# sdr_3157.net
KiCad netlist of a schematic drawn in EAGLE
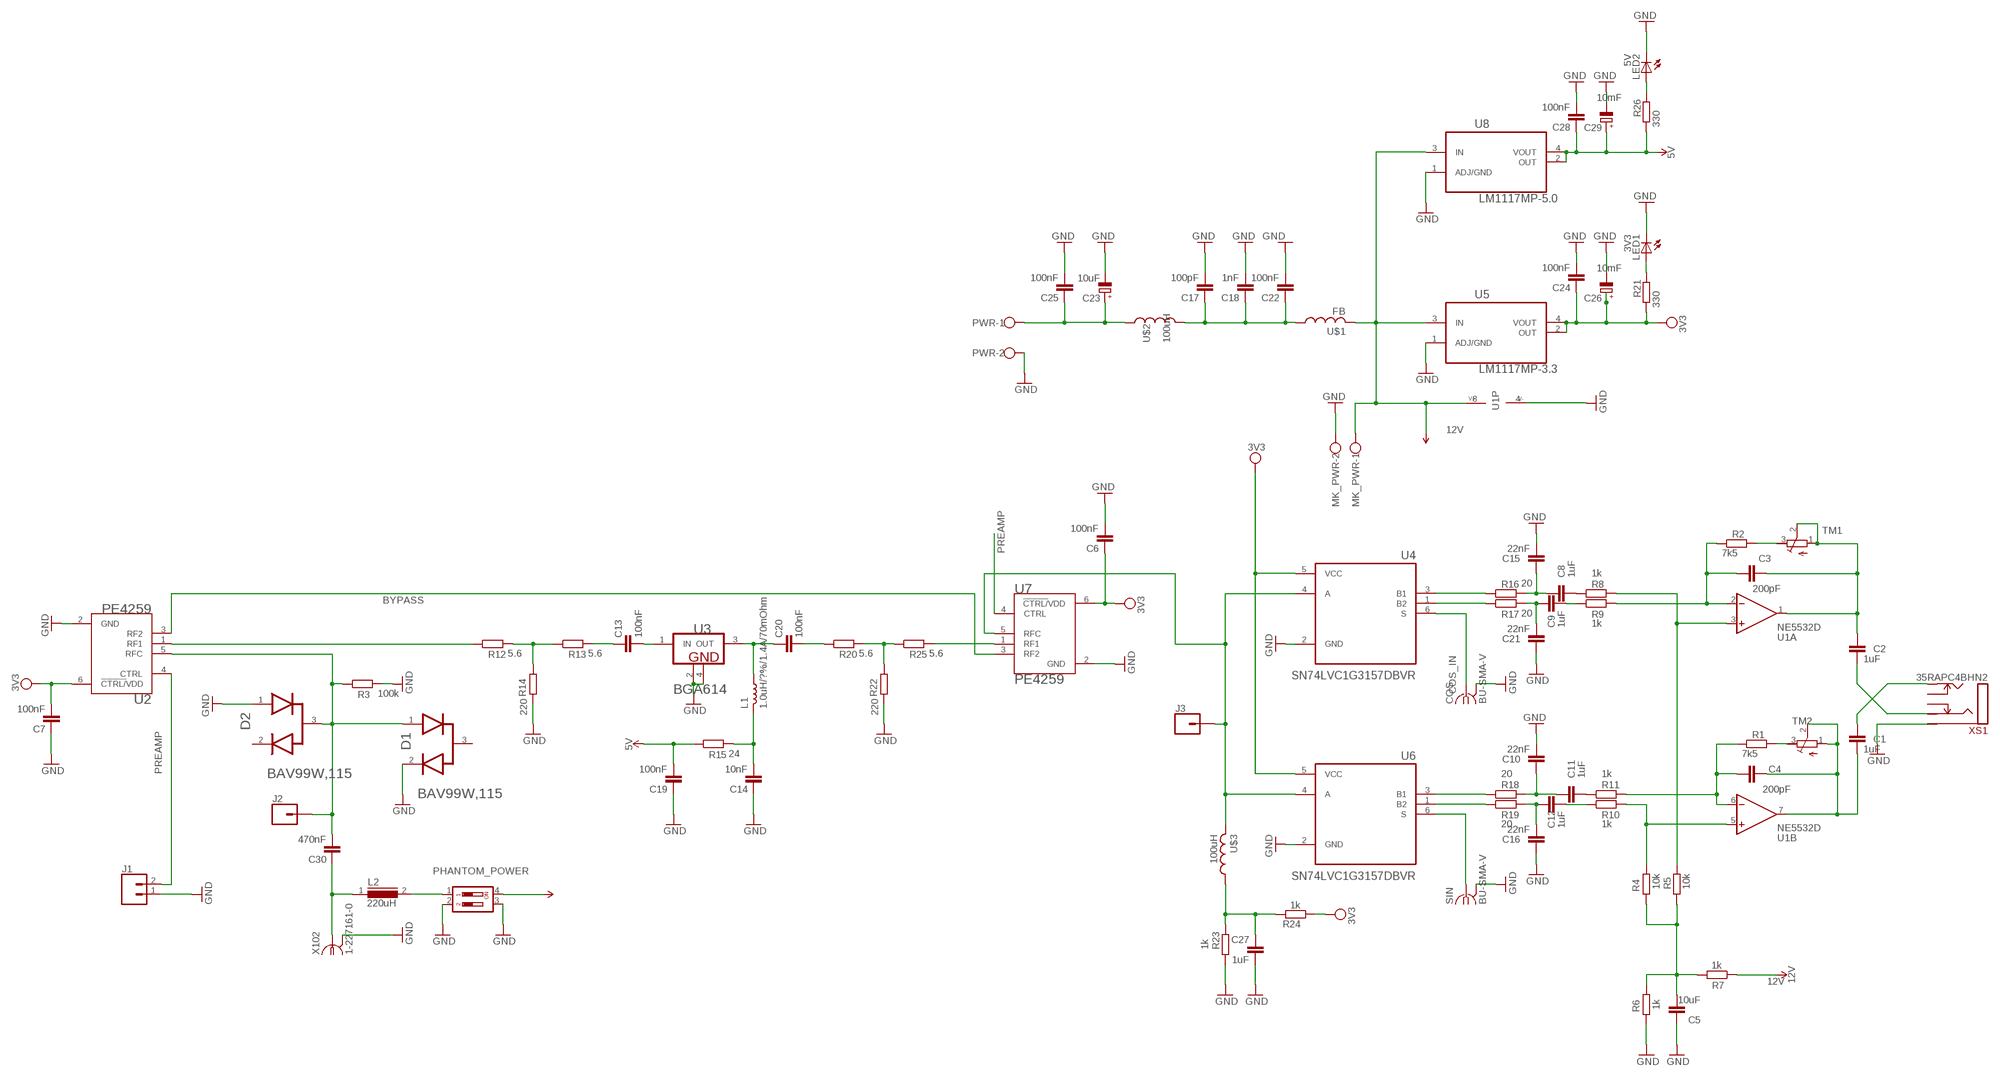
[diagram p0: schematic, sheet 1]

(export (version "E")
  (design (tool "Eeschema 10.0.6"))
  (components
    (comp (ref "C1")
      (value "1uF")
      (footprint "eagle-import:C050-045X075")
      (libsource (lib "eagle-import") (part "C-EU050-045X075"))
    )
    (comp (ref "C2")
      (value "1uF")
      (footprint "eagle-import:C050-045X075")
      (libsource (lib "eagle-import") (part "C-EU050-045X075"))
    )
    (comp (ref "C3")
      (value "200pF")
      (footprint "eagle-import:C050-045X075")
      (libsource (lib "eagle-import") (part "C-EU050-045X075"))
    )
    (comp (ref "C4")
      (value "200pF")
      (footprint "eagle-import:C050-045X075")
      (libsource (lib "eagle-import") (part "C-EU050-045X075"))
    )
    (comp (ref "C5")
      (value "10uF")
      (footprint "eagle-import:C0805")
      (libsource (lib "eagle-import") (part "C-EUC0805"))
    )
    (comp (ref "C6")
      (value "100nF")
      (footprint "eagle-import:C0805")
      (libsource (lib "eagle-import") (part "C-EUC0805"))
    )
    (comp (ref "C7")
      (value "100nF")
      (footprint "eagle-import:C0805")
      (libsource (lib "eagle-import") (part "C-EUC0805"))
    )
    (comp (ref "C8")
      (value "1uF")
      (footprint "eagle-import:C0805")
      (libsource (lib "eagle-import") (part "C-EUC0805"))
    )
    (comp (ref "C9")
      (value "1uF")
      (footprint "eagle-import:C0805")
      (libsource (lib "eagle-import") (part "C-EUC0805"))
    )
    (comp (ref "C10")
      (value "22nF")
      (footprint "eagle-import:C0805")
      (libsource (lib "eagle-import") (part "C-EUC0805"))
    )
    (comp (ref "C11")
      (value "1uF")
      (footprint "eagle-import:C0805")
      (libsource (lib "eagle-import") (part "C-EUC0805"))
    )
    (comp (ref "C12")
      (value "1uF")
      (footprint "eagle-import:C0805")
      (libsource (lib "eagle-import") (part "C-EUC0805"))
    )
    (comp (ref "C13")
      (value "100nF")
      (footprint "eagle-import:C0805")
      (libsource (lib "eagle-import") (part "C-EUC0805"))
    )
    (comp (ref "C14")
      (value "10nF")
      (footprint "eagle-import:C0805")
      (libsource (lib "eagle-import") (part "C-EUC0805"))
    )
    (comp (ref "C15")
      (value "22nF")
      (footprint "eagle-import:C0805")
      (libsource (lib "eagle-import") (part "C-EUC0805"))
    )
    (comp (ref "C16")
      (value "22nF")
      (footprint "eagle-import:C0805")
      (libsource (lib "eagle-import") (part "C-EUC0805"))
    )
    (comp (ref "C17")
      (value "100pF")
      (footprint "eagle-import:C0805")
      (libsource (lib "eagle-import") (part "C-EUC0805"))
    )
    (comp (ref "C18")
      (value "1nF")
      (footprint "eagle-import:C0805")
      (libsource (lib "eagle-import") (part "C-EUC0805"))
    )
    (comp (ref "C19")
      (value "100nF")
      (footprint "eagle-import:C0805")
      (libsource (lib "eagle-import") (part "C-EUC0805"))
    )
    (comp (ref "C20")
      (value "100nF")
      (footprint "eagle-import:C0805")
      (libsource (lib "eagle-import") (part "C-EUC0805"))
    )
    (comp (ref "C21")
      (value "22nF")
      (footprint "eagle-import:C0805")
      (libsource (lib "eagle-import") (part "C-EUC0805"))
    )
    (comp (ref "C22")
      (value "100nF")
      (footprint "eagle-import:C0805")
      (libsource (lib "eagle-import") (part "C-EUC0805"))
    )
    (comp (ref "C23")
      (value "10uF")
      (footprint "eagle-import:SMC_C")
      (libsource (lib "eagle-import") (part "CPOL-EUSMCC"))
    )
    (comp (ref "C24")
      (value "100nF")
      (footprint "eagle-import:C0805")
      (libsource (lib "eagle-import") (part "C-EUC0805"))
    )
    (comp (ref "C25")
      (value "100nF")
      (footprint "eagle-import:C0805")
      (libsource (lib "eagle-import") (part "C-EUC0805"))
    )
    (comp (ref "C26")
      (value "10mF")
      (footprint "eagle-import:SMC_C")
      (libsource (lib "eagle-import") (part "CPOL-EUSMCC"))
    )
    (comp (ref "C27")
      (value "1uF")
      (footprint "eagle-import:C0805")
      (libsource (lib "eagle-import") (part "C-EUC0805"))
    )
    (comp (ref "C28")
      (value "100nF")
      (footprint "eagle-import:C0805")
      (libsource (lib "eagle-import") (part "C-EUC0805"))
    )
    (comp (ref "C29")
      (value "10mF")
      (footprint "eagle-import:SMC_C")
      (libsource (lib "eagle-import") (part "CPOL-EUSMCC"))
    )
    (comp (ref "C30")
      (value "470nF")
      (footprint "eagle-import:C0805")
      (libsource (lib "eagle-import") (part "C-EUC0805"))
    )
    (comp (ref "COS")
      (value "BU-SMA-V")
      (footprint "eagle-import:BU-SMA-V")
      (libsource (lib "eagle-import") (part "BU-SMA-V"))
    )
    (comp (ref "D1")
      (value "NEXPERIA_BAV99W,115NEXPERIA_BAV99W,115_0_0")
      (footprint "eagle-import:NEXPERIA_BAV99W,115_0")
      (fields
        (field (name "3DS_PART_NUMBER") "412-00001")
        (field (name "DIGIKEY_PART_NUMBER") "1727-2915-1-ND")
        (field (name "MF") "Nexperia")
      )
      (libsource (lib "eagle-import") (part "NEXPERIA_BAV99W,115NEXPERIA_BAV99W,115_0_0"))
    )
    (comp (ref "D2")
      (value "NEXPERIA_BAV99W,115NEXPERIA_BAV99W,115_0_0")
      (footprint "eagle-import:NEXPERIA_BAV99W,115_0")
      (fields
        (field (name "3DS_PART_NUMBER") "412-00001")
        (field (name "DIGIKEY_PART_NUMBER") "1727-2915-1-ND")
        (field (name "MF") "Nexperia")
      )
      (libsource (lib "eagle-import") (part "NEXPERIA_BAV99W,115NEXPERIA_BAV99W,115_0_0"))
    )
    (comp (ref "J1")
      (value "CONN_02")
      (footprint "eagle-import:1X02")
      (libsource (lib "eagle-import") (part "CONN_02"))
    )
    (comp (ref "J2")
      (value "CONN_01PTH_NO_SILK_SMALL")
      (footprint "eagle-import:1X01_SMALL")
      (libsource (lib "eagle-import") (part "CONN_01PTH_NO_SILK_SMALL"))
    )
    (comp (ref "J3")
      (value "CONN_01PTH_NO_SILK_SMALL")
      (footprint "eagle-import:1X01_SMALL")
      (libsource (lib "eagle-import") (part "CONN_01PTH_NO_SILK_SMALL"))
    )
    (comp (ref "L1")
      (value "1.0uH/?%/1.4A/70mOhm")
      (footprint "eagle-import:0805-WIDE")
      (libsource (lib "eagle-import") (part "INDUCTOR-0805_WIDE-1.0UH"))
    )
    (comp (ref "L2")
      (value "220uH")
      (footprint "eagle-import:DR73")
      (libsource (lib "eagle-import") (part "DR73"))
    )
    (comp (ref "LED1")
      (value "3V3")
      (footprint "eagle-import:1206")
      (libsource (lib "eagle-import") (part "LEDSMT1206"))
    )
    (comp (ref "LED2")
      (value "5V")
      (footprint "eagle-import:1206")
      (libsource (lib "eagle-import") (part "LEDSMT1206"))
    )
    (comp (ref "MK_PWR")
      (value "W237-102")
      (footprint "eagle-import:W237-102")
      (fields (field (name "MPN") "237-102"))
      (libsource (lib "eagle-import") (part "W237-102"))
    )
    (comp (ref "PHANTOM_POWER")
      (value "DIP02YL")
      (footprint "eagle-import:DIP02YL")
      (libsource (lib "eagle-import") (part "DIP02YL"))
    )
    (comp (ref "PWR")
      (value "W237-102")
      (footprint "eagle-import:W237-102")
      (fields (field (name "MPN") "237-102"))
      (libsource (lib "eagle-import") (part "W237-102"))
    )
    (comp (ref "R1")
      (value "7k5")
      (footprint "eagle-import:R0805")
      (libsource (lib "eagle-import") (part "R-EU_R0805"))
    )
    (comp (ref "R2")
      (value "7k5")
      (footprint "eagle-import:R0805")
      (libsource (lib "eagle-import") (part "R-EU_R0805"))
    )
    (comp (ref "R3")
      (value "100k")
      (footprint "eagle-import:R0805")
      (libsource (lib "eagle-import") (part "R-EU_R0805"))
    )
    (comp (ref "R4")
      (value "10k")
      (footprint "eagle-import:M0805")
      (libsource (lib "eagle-import") (part "R-EU_M0805"))
    )
    (comp (ref "R5")
      (value "10k")
      (footprint "eagle-import:R0805")
      (libsource (lib "eagle-import") (part "R-EU_R0805"))
    )
    (comp (ref "R6")
      (value "1k")
      (footprint "eagle-import:M0805")
      (libsource (lib "eagle-import") (part "R-EU_M0805"))
    )
    (comp (ref "R7")
      (value "1k")
      (footprint "eagle-import:M0805")
      (libsource (lib "eagle-import") (part "R-EU_M0805"))
    )
    (comp (ref "R8")
      (value "1k")
      (footprint "eagle-import:R0805")
      (libsource (lib "eagle-import") (part "R-EU_R0805"))
    )
    (comp (ref "R9")
      (value "1k")
      (footprint "eagle-import:R0805")
      (libsource (lib "eagle-import") (part "R-EU_R0805"))
    )
    (comp (ref "R10")
      (value "1k")
      (footprint "eagle-import:R0805")
      (libsource (lib "eagle-import") (part "R-EU_R0805"))
    )
    (comp (ref "R11")
      (value "1k")
      (footprint "eagle-import:M0805")
      (libsource (lib "eagle-import") (part "R-EU_M0805"))
    )
    (comp (ref "R12")
      (value "5.6")
      (footprint "eagle-import:R0805")
      (libsource (lib "eagle-import") (part "R-EU_R0805"))
    )
    (comp (ref "R13")
      (value "5.6")
      (footprint "eagle-import:R0805")
      (libsource (lib "eagle-import") (part "R-EU_R0805"))
    )
    (comp (ref "R14")
      (value "220")
      (footprint "eagle-import:R0805")
      (libsource (lib "eagle-import") (part "R-EU_R0805"))
    )
    (comp (ref "R15")
      (value "24")
      (footprint "eagle-import:R0805")
      (libsource (lib "eagle-import") (part "R-EU_R0805"))
    )
    (comp (ref "R16")
      (value "20")
      (footprint "eagle-import:R0805")
      (libsource (lib "eagle-import") (part "R-EU_R0805"))
    )
    (comp (ref "R17")
      (value "20")
      (footprint "eagle-import:R0805")
      (libsource (lib "eagle-import") (part "R-EU_R0805"))
    )
    (comp (ref "R18")
      (value "20")
      (footprint "eagle-import:R0805")
      (libsource (lib "eagle-import") (part "R-EU_R0805"))
    )
    (comp (ref "R19")
      (value "20")
      (footprint "eagle-import:R0805")
      (libsource (lib "eagle-import") (part "R-EU_R0805"))
    )
    (comp (ref "R20")
      (value "5.6")
      (footprint "eagle-import:R0805")
      (libsource (lib "eagle-import") (part "R-EU_R0805"))
    )
    (comp (ref "R21")
      (value "330")
      (footprint "eagle-import:R0805")
      (libsource (lib "eagle-import") (part "R-EU_R0805"))
    )
    (comp (ref "R22")
      (value "220")
      (footprint "eagle-import:R0805")
      (libsource (lib "eagle-import") (part "R-EU_R0805"))
    )
    (comp (ref "R23")
      (value "1k")
      (footprint "eagle-import:R0805")
      (libsource (lib "eagle-import") (part "R-EU_R0805"))
    )
    (comp (ref "R24")
      (value "1k")
      (footprint "eagle-import:R0805")
      (libsource (lib "eagle-import") (part "R-EU_R0805"))
    )
    (comp (ref "R25")
      (value "5.6")
      (footprint "eagle-import:R0805")
      (libsource (lib "eagle-import") (part "R-EU_R0805"))
    )
    (comp (ref "R26")
      (value "330")
      (footprint "eagle-import:R0805")
      (libsource (lib "eagle-import") (part "R-EU_R0805"))
    )
    (comp (ref "SIN")
      (value "BU-SMA-V")
      (footprint "eagle-import:BU-SMA-V")
      (libsource (lib "eagle-import") (part "BU-SMA-V"))
    )
    (comp (ref "TM1")
      (value "5k")
      (footprint "eagle-import:RTRIM3296W")
      (libsource (lib "eagle-import") (part "R-TRIMM3296W"))
    )
    (comp (ref "TM2")
      (value "5k")
      (footprint "eagle-import:RTRIM3296W")
      (libsource (lib "eagle-import") (part "R-TRIMM3296W"))
    )
    (comp (ref "U$1") (value "FB") (footprint "eagle-import:FB") (libsource (lib "eagle-import") (part "FB")))
    (comp (ref "U$2")
      (value "100uH")
      (footprint "eagle-import:IHLP4040")
      (libsource (lib "eagle-import") (part "IHLP4040"))
    )
    (comp (ref "U$3")
      (value "100uH")
      (footprint "eagle-import:LQH55")
      (libsource (lib "eagle-import") (part "L-LQH55"))
    )
    (comp (ref "U1")
      (value "NE5532D")
      (footprint "eagle-import:SO08")
      (libsource (lib "eagle-import") (part "NE5532D"))
    )
    (comp (ref "U2")
      (value "PE4259")
      (footprint "eagle-import:SOT65P215X110-6N")
      (fields (field (name "MF") "pSemi"))
      (libsource (lib "eagle-import") (part "PE4259"))
    )
    (comp (ref "U3")
      (value "INFINEON_BGA614INFINEON_BGA614_0_0")
      (footprint "eagle-import:INFINEON_BGA614_0")
      (fields (field (name "MF") "Infineon") (field (name "MPN") "BGA614"))
      (libsource (lib "eagle-import") (part "INFINEON_BGA614INFINEON_BGA614_0_0"))
    )
    (comp (ref "U4")
      (value "SN74LVC1G3157DBVR")
      (footprint "eagle-import:SOT95P280X145-6N")
      (fields (field (name "MF") "Texas Instruments"))
      (libsource (lib "eagle-import") (part "SN74LVC1G3157DBVR"))
    )
    (comp (ref "U5")
      (value "LM1117MP-3.3")
      (footprint "eagle-import:SOT230P696X180-4N")
      (fields (field (name "MF") "Texas Instruments"))
      (libsource (lib "eagle-import") (part "LM1117MP-3.3"))
    )
    (comp (ref "U6")
      (value "SN74LVC1G3157DBVR")
      (footprint "eagle-import:SOT95P280X145-6N")
      (fields (field (name "MF") "Texas Instruments"))
      (libsource (lib "eagle-import") (part "SN74LVC1G3157DBVR"))
    )
    (comp (ref "U7")
      (value "PE4259")
      (footprint "eagle-import:SOT65P215X110-6N")
      (fields (field (name "MF") "pSemi"))
      (libsource (lib "eagle-import") (part "PE4259"))
    )
    (comp (ref "U8")
      (value "LM1117MP-5.0")
      (footprint "eagle-import:SOT230P696X180-4N")
      (fields (field (name "MF") "Texas Instruments") (field (name "MP") "LM1117MP-3.3"))
      (libsource (lib "eagle-import") (part "LM1117MP-3.3"))
    )
    (comp (ref "X102")
      (value "1-227161-0")
      (footprint "eagle-import:AMP_227161")
      (fields (field (name "MF") "TYCO ELECTRONICS") (field (name "MPN") "1-227161"))
      (libsource (lib "eagle-import") (part "?2271611--0"))
    )
    (comp (ref "XS1")
      (value "35RAPC4BHN2")
      (footprint "eagle-import:35RAP")
      (libsource (lib "eagle-import") (part "35RAPC4BHN2"))
    )
  )
  (nets
    (net (code "1") (name "/BYPASS") (class "Default")
      (node (ref "U2") (pin "3") (pinfunction "RF2_3") (pintype "passive"))
      (node (ref "U7") (pin "3") (pinfunction "RF2_3") (pintype "passive"))
    )
    (net (code "2") (name "/COS_IN") (class "Default")
      (node (ref "COS") (pin "1") (pinfunction "1_1") (pintype "passive"))
      (node (ref "U4") (pin "6") (pinfunction "S_6") (pintype "input"))
    )
    (net (code "3") (name "/PREAMP") (class "Default")
      (node (ref "J1") (pin "2") (pinfunction "2_2") (pintype "passive"))
      (node (ref "U2") (pin "4") (pinfunction "CTRL_4") (pintype "input"))
      (node (ref "U7") (pin "4") (pinfunction "CTRL_4") (pintype "input"))
    )
    (net (code "4") (name "3V3") (class "Default")
      (node (ref "C24") (pin "1") (pinfunction "1_1") (pintype "passive"))
      (node (ref "C26") (pin "+") (pinfunction "+_+") (pintype "passive"))
      (node (ref "C6") (pin "1") (pinfunction "1_1") (pintype "passive"))
      (node (ref "C7") (pin "2") (pinfunction "2_2") (pintype "passive"))
      (node (ref "R21") (pin "1") (pinfunction "1_1") (pintype "passive"))
      (node (ref "R24") (pin "1") (pinfunction "1_1") (pintype "passive"))
      (node (ref "U2") (pin "6") (pinfunction "~{CTRL/}VDD_6") (pintype "power_in"))
      (node (ref "U4") (pin "5") (pinfunction "VCC_5") (pintype "power_in"))
      (node (ref "U5") (pin "2") (pinfunction "OUT_2") (pintype "output"))
      (node (ref "U5") (pin "4") (pinfunction "VOUT_4") (pintype "output"))
      (node (ref "U6") (pin "5") (pinfunction "VCC_5") (pintype "power_in"))
      (node (ref "U7") (pin "6") (pinfunction "~{CTRL/}VDD_6") (pintype "power_in"))
    )
    (net (code "5") (name "5V") (class "Default")
      (node (ref "C19") (pin "2") (pinfunction "2_2") (pintype "passive"))
      (node (ref "C28") (pin "1") (pinfunction "1_1") (pintype "passive"))
      (node (ref "C29") (pin "+") (pinfunction "+_+") (pintype "passive"))
      (node (ref "R15") (pin "1") (pinfunction "1_1") (pintype "passive"))
      (node (ref "R26") (pin "1") (pinfunction "1_1") (pintype "passive"))
      (node (ref "U8") (pin "2") (pinfunction "OUT_2") (pintype "output"))
      (node (ref "U8") (pin "4") (pinfunction "VOUT_4") (pintype "output"))
    )
    (net (code "6") (name "12V") (class "Default")
      (node (ref "MK_PWR") (pin "1") (pinfunction "KL_1") (pintype "passive"))
      (node (ref "PHANTOM_POWER") (pin "4") (pinfunction "4_4") (pintype "passive"))
      (node (ref "R7") (pin "1") (pinfunction "1_1") (pintype "passive"))
      (node (ref "U$1") (pin "P$2") (pinfunction "2_P$2") (pintype "passive"))
      (node (ref "U1") (pin "8") (pinfunction "V+_8") (pintype "power_in"))
      (node (ref "U5") (pin "3") (pinfunction "IN_3") (pintype "input"))
      (node (ref "U8") (pin "3") (pinfunction "IN_3") (pintype "input"))
    )
    (net (code "7") (name "GND") (class "Default")
      (node (ref "C10") (pin "2") (pinfunction "2_2") (pintype "passive"))
      (node (ref "C14") (pin "1") (pinfunction "1_1") (pintype "passive"))
      (node (ref "C15") (pin "2") (pinfunction "2_2") (pintype "passive"))
      (node (ref "C16") (pin "1") (pinfunction "1_1") (pintype "passive"))
      (node (ref "C17") (pin "2") (pinfunction "2_2") (pintype "passive"))
      (node (ref "C18") (pin "2") (pinfunction "2_2") (pintype "passive"))
      (node (ref "C19") (pin "1") (pinfunction "1_1") (pintype "passive"))
      (node (ref "C21") (pin "1") (pinfunction "1_1") (pintype "passive"))
      (node (ref "C22") (pin "2") (pinfunction "2_2") (pintype "passive"))
      (node (ref "C23") (pin "-") (pinfunction "-_-") (pintype "passive"))
      (node (ref "C24") (pin "2") (pinfunction "2_2") (pintype "passive"))
      (node (ref "C25") (pin "2") (pinfunction "2_2") (pintype "passive"))
      (node (ref "C26") (pin "-") (pinfunction "-_-") (pintype "passive"))
      (node (ref "C27") (pin "1") (pinfunction "1_1") (pintype "passive"))
      (node (ref "C28") (pin "2") (pinfunction "2_2") (pintype "passive"))
      (node (ref "C29") (pin "-") (pinfunction "-_-") (pintype "passive"))
      (node (ref "C5") (pin "1") (pinfunction "1_1") (pintype "passive"))
      (node (ref "C6") (pin "2") (pinfunction "2_2") (pintype "passive"))
      (node (ref "C7") (pin "1") (pinfunction "1_1") (pintype "passive"))
      (node (ref "COS") (pin "2") (pinfunction "2_2") (pintype "passive"))
      (node (ref "COS") (pin "3") (pinfunction "2_3") (pintype "passive"))
      (node (ref "COS") (pin "4") (pinfunction "2_4") (pintype "passive"))
      (node (ref "COS") (pin "5") (pinfunction "2_5") (pintype "passive"))
      (node (ref "D1") (pin "2") (pinfunction "2_CATHODE_2") (pintype "passive"))
      (node (ref "D2") (pin "1") (pinfunction "1_ANODE_1") (pintype "passive"))
      (node (ref "J1") (pin "1") (pinfunction "1_1") (pintype "passive"))
      (node (ref "LED1") (pin "C") (pinfunction "C_C") (pintype "passive"))
      (node (ref "LED2") (pin "C") (pinfunction "C_C") (pintype "passive"))
      (node (ref "MK_PWR") (pin "2") (pinfunction "KL_2") (pintype "passive"))
      (node (ref "PHANTOM_POWER") (pin "2") (pinfunction "2_2") (pintype "passive"))
      (node (ref "PHANTOM_POWER") (pin "3") (pinfunction "3_3") (pintype "passive"))
      (node (ref "PWR") (pin "2") (pinfunction "KL_2") (pintype "passive"))
      (node (ref "R14") (pin "2") (pinfunction "2_2") (pintype "passive"))
      (node (ref "R22") (pin "2") (pinfunction "2_2") (pintype "passive"))
      (node (ref "R23") (pin "1") (pinfunction "1_1") (pintype "passive"))
      (node (ref "R3") (pin "2") (pinfunction "2_2") (pintype "passive"))
      (node (ref "R6") (pin "1") (pinfunction "1_1") (pintype "passive"))
      (node (ref "SIN") (pin "2") (pinfunction "2_2") (pintype "passive"))
      (node (ref "SIN") (pin "3") (pinfunction "2_3") (pintype "passive"))
      (node (ref "SIN") (pin "4") (pinfunction "2_4") (pintype "passive"))
      (node (ref "SIN") (pin "5") (pinfunction "2_5") (pintype "passive"))
      (node (ref "U1") (pin "4") (pinfunction "V-_4") (pintype "power_in"))
      (node (ref "U2") (pin "2") (pinfunction "GND_2") (pintype "power_in"))
      (node (ref "U3") (pin "2") (pinfunction "1_GND_2") (pintype "power_in"))
      (node (ref "U3") (pin "4") (pinfunction "2_GND_4") (pintype "power_in"))
      (node (ref "U4") (pin "2") (pinfunction "GND_2") (pintype "power_in"))
      (node (ref "U5") (pin "1") (pinfunction "ADJ/GND_1") (pintype "passive"))
      (node (ref "U6") (pin "2") (pinfunction "GND_2") (pintype "power_in"))
      (node (ref "U7") (pin "2") (pinfunction "GND_2") (pintype "power_in"))
      (node (ref "U8") (pin "1") (pinfunction "ADJ/GND_1") (pintype "passive"))
      (node (ref "X102") (pin "2") (pinfunction "2_2") (pintype "passive"))
      (node (ref "XS1") (pin "1") (pinfunction "S_1") (pintype "passive"))
    )
    (net (code "8") (name "Net-(C5-Pad2)") (class "Default")
      (node (ref "C5") (pin "2") (pinfunction "2_2") (pintype "passive"))
      (node (ref "R4") (pin "1") (pinfunction "1_1") (pintype "passive"))
      (node (ref "R5") (pin "1") (pinfunction "1_1") (pintype "passive"))
      (node (ref "R6") (pin "2") (pinfunction "2_2") (pintype "passive"))
      (node (ref "R7") (pin "2") (pinfunction "2_2") (pintype "passive"))
    )
    (net (code "9") (name "Net-(C8-Pad2)") (class "Default")
      (node (ref "C8") (pin "2") (pinfunction "2_2") (pintype "passive"))
      (node (ref "R8") (pin "1") (pinfunction "1_1") (pintype "passive"))
    )
    (net (code "10") (name "Net-(C9-Pad2)") (class "Default")
      (node (ref "C9") (pin "2") (pinfunction "2_2") (pintype "passive"))
      (node (ref "R9") (pin "1") (pinfunction "1_1") (pintype "passive"))
    )
    (net (code "11") (name "Net-(C10-Pad1)") (class "Default")
      (node (ref "C10") (pin "1") (pinfunction "1_1") (pintype "passive"))
      (node (ref "C11") (pin "1") (pinfunction "1_1") (pintype "passive"))
      (node (ref "R18") (pin "2") (pinfunction "2_2") (pintype "passive"))
    )
    (net (code "12") (name "Net-(C11-Pad2)") (class "Default")
      (node (ref "C11") (pin "2") (pinfunction "2_2") (pintype "passive"))
      (node (ref "R11") (pin "1") (pinfunction "1_1") (pintype "passive"))
    )
    (net (code "13") (name "Net-(C12-Pad1)") (class "Default")
      (node (ref "C12") (pin "1") (pinfunction "1_1") (pintype "passive"))
      (node (ref "C16") (pin "2") (pinfunction "2_2") (pintype "passive"))
      (node (ref "R19") (pin "2") (pinfunction "2_2") (pintype "passive"))
    )
    (net (code "14") (name "Net-(C12-Pad2)") (class "Default")
      (node (ref "C12") (pin "2") (pinfunction "2_2") (pintype "passive"))
      (node (ref "R10") (pin "1") (pinfunction "1_1") (pintype "passive"))
    )
    (net (code "15") (name "Net-(C13-Pad1)") (class "Default")
      (node (ref "C13") (pin "1") (pinfunction "1_1") (pintype "passive"))
      (node (ref "R13") (pin "2") (pinfunction "2_2") (pintype "passive"))
    )
    (net (code "16") (name "Net-(C14-Pad2)") (class "Default")
      (node (ref "C14") (pin "2") (pinfunction "2_2") (pintype "passive"))
      (node (ref "L1") (pin "2") (pinfunction "2_2") (pintype "passive"))
      (node (ref "R15") (pin "2") (pinfunction "2_2") (pintype "passive"))
    )
    (net (code "17") (name "Net-(C15-Pad1)") (class "Default")
      (node (ref "C15") (pin "1") (pinfunction "1_1") (pintype "passive"))
      (node (ref "C8") (pin "1") (pinfunction "1_1") (pintype "passive"))
      (node (ref "R16") (pin "2") (pinfunction "2_2") (pintype "passive"))
    )
    (net (code "18") (name "Net-(C20-Pad2)") (class "Default")
      (node (ref "C20") (pin "2") (pinfunction "2_2") (pintype "passive"))
      (node (ref "R20") (pin "1") (pinfunction "1_1") (pintype "passive"))
    )
    (net (code "19") (name "Net-(C21-Pad2)") (class "Default")
      (node (ref "C21") (pin "2") (pinfunction "2_2") (pintype "passive"))
      (node (ref "C9") (pin "1") (pinfunction "1_1") (pintype "passive"))
      (node (ref "R17") (pin "2") (pinfunction "2_2") (pintype "passive"))
    )
    (net (code "20") (name "Net-(C27-Pad2)") (class "Default")
      (node (ref "C27") (pin "2") (pinfunction "2_2") (pintype "passive"))
      (node (ref "R23") (pin "2") (pinfunction "2_2") (pintype "passive"))
      (node (ref "R24") (pin "2") (pinfunction "2_2") (pintype "passive"))
      (node (ref "U$3") (pin "1") (pinfunction "1_1") (pintype "passive"))
    )
    (net (code "21") (name "Net-(C30-Pad1)") (class "Default")
      (node (ref "C30") (pin "1") (pinfunction "1_1") (pintype "passive"))
      (node (ref "L2") (pin "1") (pinfunction "1_1") (pintype "passive"))
      (node (ref "X102") (pin "1") (pinfunction "1_1") (pintype "passive"))
    )
    (net (code "22") (name "Net-(D1-1_ANODE)") (class "Default")
      (node (ref "C30") (pin "2") (pinfunction "2_2") (pintype "passive"))
      (node (ref "D1") (pin "1") (pinfunction "1_ANODE_1") (pintype "passive"))
      (node (ref "D2") (pin "3") (pinfunction "1_CATHODE/2_ANODE_3") (pintype "passive"))
      (node (ref "J2") (pin "P$1") (pinfunction "1_P$1") (pintype "passive"))
      (node (ref "R3") (pin "1") (pinfunction "1_1") (pintype "passive"))
      (node (ref "U2") (pin "5") (pinfunction "RFC_5") (pintype "passive"))
    )
    (net (code "23") (name "Net-(J3-1)") (class "Default")
      (node (ref "J3") (pin "P$1") (pinfunction "1_P$1") (pintype "passive"))
      (node (ref "U$3") (pin "2") (pinfunction "2_2") (pintype "passive"))
      (node (ref "U4") (pin "4") (pinfunction "A_4") (pintype "output"))
      (node (ref "U6") (pin "4") (pinfunction "A_4") (pintype "output"))
      (node (ref "U7") (pin "5") (pinfunction "RFC_5") (pintype "passive"))
    )
    (net (code "24") (name "Net-(L2-Pad2)") (class "Default")
      (node (ref "L2") (pin "2") (pinfunction "2_2") (pintype "passive"))
      (node (ref "PHANTOM_POWER") (pin "1") (pinfunction "1_1") (pintype "passive"))
    )
    (net (code "25") (name "Net-(LED1-PadA)") (class "Default")
      (node (ref "LED1") (pin "A") (pinfunction "A_A") (pintype "passive"))
      (node (ref "R21") (pin "2") (pinfunction "2_2") (pintype "passive"))
    )
    (net (code "26") (name "Net-(LED2-PadA)") (class "Default")
      (node (ref "LED2") (pin "A") (pinfunction "A_A") (pintype "passive"))
      (node (ref "R26") (pin "2") (pinfunction "2_2") (pintype "passive"))
    )
    (net (code "27") (name "Net-(PWRA-KL)") (class "Default")
      (node (ref "C23") (pin "+") (pinfunction "+_+") (pintype "passive"))
      (node (ref "C25") (pin "1") (pinfunction "1_1") (pintype "passive"))
      (node (ref "PWR") (pin "1") (pinfunction "KL_1") (pintype "passive"))
      (node (ref "U$2") (pin "1") (pinfunction "1_1") (pintype "passive"))
    )
    (net (code "28") (name "Net-(R12-Pad2)") (class "Default")
      (node (ref "R12") (pin "2") (pinfunction "2_2") (pintype "passive"))
      (node (ref "R13") (pin "1") (pinfunction "1_1") (pintype "passive"))
      (node (ref "R14") (pin "1") (pinfunction "1_1") (pintype "passive"))
    )
    (net (code "29") (name "Net-(R20-Pad2)") (class "Default")
      (node (ref "R20") (pin "2") (pinfunction "2_2") (pintype "passive"))
      (node (ref "R22") (pin "1") (pinfunction "1_1") (pintype "passive"))
      (node (ref "R25") (pin "1") (pinfunction "1_1") (pintype "passive"))
    )
    (net (code "30") (name "Net-(TM1-A)") (class "Default")
      (node (ref "C2") (pin "1") (pinfunction "1_1") (pintype "passive"))
      (node (ref "C3") (pin "2") (pinfunction "2_2") (pintype "passive"))
      (node (ref "TM1") (pin "1") (pinfunction "A_1") (pintype "passive"))
      (node (ref "TM1") (pin "2") (pinfunction "S_2") (pintype "passive"))
      (node (ref "U1") (pin "1") (pinfunction "OUT_1") (pintype "output"))
    )
    (net (code "31") (name "Net-(TM1-E)") (class "Default")
      (node (ref "R2") (pin "2") (pinfunction "2_2") (pintype "passive"))
      (node (ref "TM1") (pin "3") (pinfunction "E_3") (pintype "passive"))
    )
    (net (code "32") (name "Net-(TM2-A)") (class "Default")
      (node (ref "C1") (pin "2") (pinfunction "2_2") (pintype "passive"))
      (node (ref "C4") (pin "2") (pinfunction "2_2") (pintype "passive"))
      (node (ref "TM2") (pin "1") (pinfunction "A_1") (pintype "passive"))
      (node (ref "TM2") (pin "2") (pinfunction "S_2") (pintype "passive"))
      (node (ref "U1") (pin "7") (pinfunction "OUT_7") (pintype "output"))
    )
    (net (code "33") (name "Net-(TM2-E)") (class "Default")
      (node (ref "R1") (pin "2") (pinfunction "2_2") (pintype "passive"))
      (node (ref "TM2") (pin "3") (pinfunction "E_3") (pintype "passive"))
    )
    (net (code "34") (name "Net-(U$1-1)") (class "Default")
      (node (ref "C17") (pin "1") (pinfunction "1_1") (pintype "passive"))
      (node (ref "C18") (pin "1") (pinfunction "1_1") (pintype "passive"))
      (node (ref "C22") (pin "1") (pinfunction "1_1") (pintype "passive"))
      (node (ref "U$1") (pin "P$1") (pinfunction "1_P$1") (pintype "passive"))
      (node (ref "U$2") (pin "2") (pinfunction "2_2") (pintype "passive"))
    )
    (net (code "35") (name "Net-(U1A-+IN)") (class "Default")
      (node (ref "R5") (pin "2") (pinfunction "2_2") (pintype "passive"))
      (node (ref "R8") (pin "2") (pinfunction "2_2") (pintype "passive"))
      (node (ref "U1") (pin "3") (pinfunction "+IN_3") (pintype "input"))
    )
    (net (code "36") (name "Net-(U1A--IN)") (class "Default")
      (node (ref "C3") (pin "1") (pinfunction "1_1") (pintype "passive"))
      (node (ref "R2") (pin "1") (pinfunction "1_1") (pintype "passive"))
      (node (ref "R9") (pin "2") (pinfunction "2_2") (pintype "passive"))
      (node (ref "U1") (pin "2") (pinfunction "-IN_2") (pintype "input"))
    )
    (net (code "37") (name "Net-(U1B-+IN)") (class "Default")
      (node (ref "R10") (pin "2") (pinfunction "2_2") (pintype "passive"))
      (node (ref "R4") (pin "2") (pinfunction "2_2") (pintype "passive"))
      (node (ref "U1") (pin "5") (pinfunction "+IN_5") (pintype "input"))
    )
    (net (code "38") (name "Net-(U1B--IN)") (class "Default")
      (node (ref "C4") (pin "1") (pinfunction "1_1") (pintype "passive"))
      (node (ref "R1") (pin "1") (pinfunction "1_1") (pintype "passive"))
      (node (ref "R11") (pin "2") (pinfunction "2_2") (pintype "passive"))
      (node (ref "U1") (pin "6") (pinfunction "-IN_6") (pintype "input"))
    )
    (net (code "39") (name "Net-(U2-RF1)") (class "Default")
      (node (ref "R12") (pin "1") (pinfunction "1_1") (pintype "passive"))
      (node (ref "U2") (pin "1") (pinfunction "RF1_1") (pintype "passive"))
    )
    (net (code "40") (name "Net-(U3-IN)") (class "Default")
      (node (ref "C13") (pin "2") (pinfunction "2_2") (pintype "passive"))
      (node (ref "U3") (pin "1") (pinfunction "IN_1") (pintype "input"))
    )
    (net (code "41") (name "Net-(U3-OUT)") (class "Default")
      (node (ref "C20") (pin "1") (pinfunction "1_1") (pintype "passive"))
      (node (ref "L1") (pin "1") (pinfunction "1_1") (pintype "passive"))
      (node (ref "U3") (pin "3") (pinfunction "OUT_3") (pintype "output"))
    )
    (net (code "42") (name "Net-(U4-B1)") (class "Default")
      (node (ref "R16") (pin "1") (pinfunction "1_1") (pintype "passive"))
      (node (ref "U4") (pin "3") (pinfunction "B1_3") (pintype "input"))
    )
    (net (code "43") (name "Net-(U4-B2)") (class "Default")
      (node (ref "R17") (pin "1") (pinfunction "1_1") (pintype "passive"))
      (node (ref "U4") (pin "1") (pinfunction "B2_1") (pintype "input"))
    )
    (net (code "44") (name "Net-(U6-B1)") (class "Default")
      (node (ref "R18") (pin "1") (pinfunction "1_1") (pintype "passive"))
      (node (ref "U6") (pin "3") (pinfunction "B1_3") (pintype "input"))
    )
    (net (code "45") (name "Net-(U6-B2)") (class "Default")
      (node (ref "R19") (pin "1") (pinfunction "1_1") (pintype "passive"))
      (node (ref "U6") (pin "1") (pinfunction "B2_1") (pintype "input"))
    )
    (net (code "46") (name "Net-(U6-S)") (class "Default")
      (node (ref "SIN") (pin "1") (pinfunction "1_1") (pintype "passive"))
      (node (ref "U6") (pin "6") (pinfunction "S_6") (pintype "input"))
    )
    (net (code "47") (name "Net-(U7-RF1)") (class "Default")
      (node (ref "R25") (pin "2") (pinfunction "2_2") (pintype "passive"))
      (node (ref "U7") (pin "1") (pinfunction "RF1_1") (pintype "passive"))
    )
    (net (code "48") (name "Net-(XS1-R)") (class "Default")
      (node (ref "C2") (pin "2") (pinfunction "2_2") (pintype "passive"))
      (node (ref "XS1") (pin "3") (pinfunction "R_3") (pintype "passive"))
    )
    (net (code "49") (name "Net-(XS1-T)") (class "Default")
      (node (ref "C1") (pin "1") (pinfunction "1_1") (pintype "passive"))
      (node (ref "XS1") (pin "2") (pinfunction "T_2") (pintype "passive"))
    )
    (net (code "50") (name "unconnected-(D1-1_CATHODE{slash}2_ANODE-Pad3)") (class "Default")
      (node (ref "D1") (pin "3") (pinfunction "1_CATHODE/2_ANODE_3") (pintype "passive"))
    )
    (net (code "51") (name "unconnected-(D2-2_CATHODE-Pad2)") (class "Default")
      (node (ref "D2") (pin "2") (pinfunction "2_CATHODE_2") (pintype "passive"))
    )
    (net (code "52") (name "unconnected-(XS1-RN-Pad11)") (class "Default")
      (node (ref "XS1") (pin "11") (pinfunction "RN_11") (pintype "passive"))
    )
    (net (code "53") (name "unconnected-(XS1-TN-Pad10)") (class "Default")
      (node (ref "XS1") (pin "10") (pinfunction "TN_10") (pintype "passive"))
    )
  )
)
